# NPNTransistorElement.net
KiCad netlist of a schematic drawn in Altium Designer
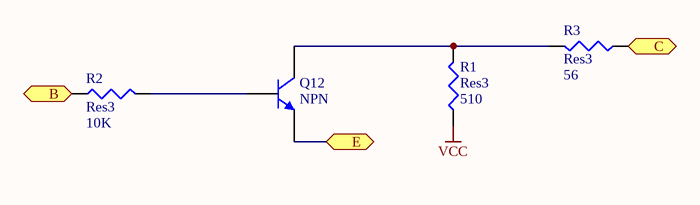
[diagram p0: NPNTransistorElement.SchDoc]

(export (version "E")
  (design (tool "Eeschema 10.0.6"))
  (components
    (comp (ref "Q12")
      (value "NPN")
      (footprint "SOT95P230-3N")
      (description "NPN Bipolar Transistor")
      (fields (field (name "PUBLISHER") "Altium Limited"))
      (libsource (lib "MIDIPiano") (part "NPN"))
    )
    (comp (ref "R1")
      (value "Res3")
      (footprint "J1-0603")
      (description "Resistor")
      (fields (field (name "ALTIUM_VALUE") "510") (field (name "PUBLISHER") "Altium Limited"))
      (libsource (lib "MIDIPiano") (part "Res3"))
    )
    (comp (ref "R2")
      (value "Res3")
      (footprint "J1-0603")
      (description "Resistor")
      (fields (field (name "ALTIUM_VALUE") "10K") (field (name "PUBLISHER") "Altium Limited"))
      (libsource (lib "MIDIPiano") (part "Res3"))
    )
    (comp (ref "R3")
      (value "Res3")
      (footprint "J1-0603")
      (description "Resistor")
      (fields (field (name "ALTIUM_VALUE") "56") (field (name "PUBLISHER") "Altium Limited"))
      (libsource (lib "MIDIPiano") (part "Res3"))
    )
  )
  (nets
    (net (code "1") (name "/B") (class "Default")
      (node (ref "R2") (pin "1") (pinfunction "1_1") (pintype "passive"))
    )
    (net (code "2") (name "/C") (class "Default")
      (node (ref "R3") (pin "1") (pinfunction "1_1") (pintype "passive"))
    )
    (net (code "3") (name "/E") (class "Default")
      (node (ref "Q12") (pin "3") (pinfunction "E_3") (pintype "passive"))
    )
    (net (code "4") (name "Net-(Q12-B)") (class "Default")
      (node (ref "Q12") (pin "2") (pinfunction "B_2") (pintype "passive"))
      (node (ref "R2") (pin "2") (pinfunction "2_2") (pintype "passive"))
    )
    (net (code "5") (name "Net-(Q12-C)") (class "Default")
      (node (ref "Q12") (pin "1") (pinfunction "C_1") (pintype "passive"))
      (node (ref "R1") (pin "2") (pinfunction "2_2") (pintype "passive"))
      (node (ref "R3") (pin "2") (pinfunction "2_2") (pintype "passive"))
    )
    (net (code "6") (name "VCC") (class "Default")
      (node (ref "R1") (pin "1") (pinfunction "1_1") (pintype "passive"))
    )
  )
)
